# PowerSupply.net
KiCad netlist of a schematic drawn in Altium Designer
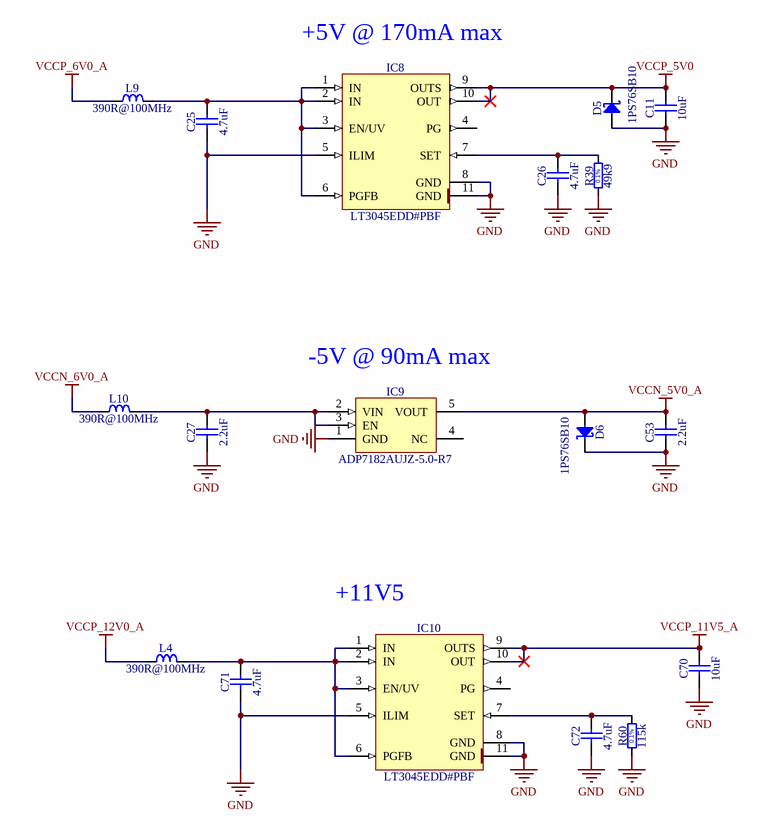
[diagram p0: PowerSupply.SchDoc]

(export (version "E")
  (design (tool "Eeschema 10.0.6"))
  (components
    (comp (ref "C11")
      (value "10uF")
      (footprint "CAPC1608X87N")
      (description "Non-polarised capacitor")
      (fields
        (field (name "PART NUMBER") "CC0603_10UF_6.3V_20%_X5R")
        (field (name "VOLTAGE") "6.3V")
        (field (name "AUTHOR") "CERN DEM JLC")
      )
      (libsource (lib "Capacitors") (part "Capacitor - non polarized"))
    )
    (comp (ref "C25")
      (value "4.7uF")
      (footprint "CAPC1709X95N")
      (description "Non-polarised capacitor")
      (fields
        (field (name "PART NUMBER") "CC0603_4.7UF_16V_10%_X5R")
        (field (name "VOLTAGE") "16V")
        (field (name "AUTHOR") "CERN DEM JLC")
      )
      (libsource (lib "Capacitors") (part "Capacitor - non polarized"))
    )
    (comp (ref "C26")
      (value "4.7uF")
      (footprint "CAPC1709X95N")
      (description "Non-polarised capacitor")
      (fields
        (field (name "PART NUMBER") "CC0603_4.7UF_16V_10%_X5R")
        (field (name "VOLTAGE") "16V")
        (field (name "AUTHOR") "CERN DEM JLC")
      )
      (libsource (lib "Capacitors") (part "Capacitor - non polarized"))
    )
    (comp (ref "C27")
      (value "2.2uF")
      (footprint "CAPC1608X90N")
      (description "Non-polarised capacitor")
      (fields
        (field (name "PART NUMBER") "CC0603_2.2UF_10V_20%_X7R")
        (field (name "VOLTAGE") "10V")
        (field (name "AUTHOR") "CERN DEM JLC")
      )
      (libsource (lib "Capacitors") (part "Capacitor - non polarized"))
    )
    (comp (ref "C53")
      (value "2.2uF")
      (footprint "CAPC1608X90N")
      (description "Non-polarised capacitor")
      (fields
        (field (name "PART NUMBER") "CC0603_2.2UF_10V_20%_X7R")
        (field (name "VOLTAGE") "10V")
        (field (name "AUTHOR") "CERN DEM JLC")
      )
      (libsource (lib "Capacitors") (part "Capacitor - non polarized"))
    )
    (comp (ref "C70")
      (value "10uF")
      (footprint "CAPC1608X87N")
      (description "Non-polarised capacitor")
      (fields
        (field (name "PART NUMBER") "CC0603_10UF_6.3V_20%_X5R")
        (field (name "VOLTAGE") "6.3V")
        (field (name "AUTHOR") "CERN DEM JLC")
      )
      (libsource (lib "Capacitors") (part "Capacitor - non polarized"))
    )
    (comp (ref "C71")
      (value "4.7uF")
      (footprint "CAPC1709X95N")
      (description "Non-polarised capacitor")
      (fields
        (field (name "PART NUMBER") "CC0603_4.7UF_16V_10%_X5R")
        (field (name "VOLTAGE") "16V")
        (field (name "AUTHOR") "CERN DEM JLC")
      )
      (libsource (lib "Capacitors") (part "Capacitor - non polarized"))
    )
    (comp (ref "C72")
      (value "4.7uF")
      (footprint "CAPC1709X95N")
      (description "Non-polarised capacitor")
      (fields
        (field (name "PART NUMBER") "CC0603_4.7UF_16V_10%_X5R")
        (field (name "VOLTAGE") "16V")
        (field (name "AUTHOR") "CERN DEM JLC")
      )
      (libsource (lib "Capacitors") (part "Capacitor - non polarized"))
    )
    (comp (ref "D5")
      (value "1PS76SB10")
      (footprint "SOD2512X110N")
      (description "Schottky Diode")
      (fields
        (field (name "VOLTAGE") "30V")
        (field (name "POWER") "200mA")
        (field (name "AUTHOR") "CERN DEM JLC")
      )
      (libsource (lib "ICs And Semiconductors") (part "Diode Schottky"))
    )
    (comp (ref "D6")
      (value "1PS76SB10")
      (footprint "SOD2512X110N")
      (description "Schottky Diode")
      (fields
        (field (name "VOLTAGE") "30V")
        (field (name "POWER") "200mA")
        (field (name "AUTHOR") "CERN DEM JLC")
      )
      (libsource (lib "ICs And Semiconductors") (part "Diode Schottky"))
    )
    (comp (ref "IC8")
      (value "LT3045EDD#PBF")
      (footprint "SON50P300X300X80-11N-R175X248")
      (description "20V, 500mA, Ultralow Noise, Ultrahigh PSRR Linear Regulator")
      (fields (field (name "MANUFACTURER") "LINEAR TECHNOLOGY") (field (name "AUTHOR") "CERN DEM JLC"))
      (libsource (lib "ICs And Semiconductors") (part "LT3045EDD"))
    )
    (comp (ref "IC9")
      (value "ADP7182AUJZ-5.0-R7")
      (footprint "SOT95P280X90-5N")
      (description "–5V, 200 mA, Low Noise, Linear Regulator")
      (fields (field (name "MANUFACTURER") "ANALOG DEVICES") (field (name "AUTHOR") "CERN DEM JLC"))
      (libsource (lib "ICs And Semiconductors") (part "ADP7182AUJZ-X.X-R7"))
    )
    (comp (ref "IC10")
      (value "LT3045EDD#PBF")
      (footprint "SON50P300X300X80-11N-R175X248")
      (description "20V, 500mA, Ultralow Noise, Ultrahigh PSRR Linear Regulator")
      (fields (field (name "MANUFACTURER") "LINEAR TECHNOLOGY") (field (name "AUTHOR") "CERN DEM JLC"))
      (libsource (lib "ICs And Semiconductors") (part "LT3045EDD"))
    )
    (comp (ref "L4")
      (value "390R@100MHz")
      (footprint "INDC1608X95N")
      (description "Inductor")
      (fields
        (field (name "PART NUMBER") "IND0603_TDK_MPZ1608R391A")
        (field (name "POWER") "1.2A")
        (field (name "AUTHOR") "CERN DEM JLC")
      )
      (libsource (lib "Inductors & Transformers") (part "Inductor"))
    )
    (comp (ref "L9")
      (value "390R@100MHz")
      (footprint "INDC1608X95N")
      (description "Inductor")
      (fields
        (field (name "PART NUMBER") "IND0603_TDK_MPZ1608R391A")
        (field (name "POWER") "1.2A")
        (field (name "AUTHOR") "CERN DEM JLC")
      )
      (libsource (lib "Inductors & Transformers") (part "Inductor"))
    )
    (comp (ref "L10")
      (value "390R@100MHz")
      (footprint "INDC1608X95N")
      (description "Inductor")
      (fields
        (field (name "PART NUMBER") "IND0603_TDK_MPZ1608R391A")
        (field (name "POWER") "1.2A")
        (field (name "AUTHOR") "CERN DEM JLC")
      )
      (libsource (lib "Inductors & Transformers") (part "Inductor"))
    )
    (comp (ref "R39")
      (value "49k9")
      (footprint "RESC1608X55N")
      (description "Resistor - 0.1%")
      (fields
        (field (name "PART NUMBER") "R0603_49K9_0.1%_0.063W_10PPM")
        (field (name "POWER") "0.063W")
        (field (name "AUTHOR") "CERN DEM JLC")
      )
      (libsource (lib "Resistors") (part "Resistor - 0.1%"))
    )
    (comp (ref "R60")
      (value "115k")
      (footprint "RESC1608X55N")
      (description "Resistor - 0.1%")
      (fields
        (field (name "PART NUMBER") "R0603_115K_0.1%_0.063W_10PPM")
        (field (name "POWER") "0.063W")
        (field (name "AUTHOR") "CERN DEM JLC")
      )
      (libsource (lib "Resistors") (part "Resistor - 0.1%"))
    )
  )
  (nets
    (net (code "1") (name "GND") (class "Default")
      (node (ref "C11") (pin "1") (pinfunction "1_1") (pintype "passive"))
      (node (ref "C25") (pin "1") (pinfunction "1_1") (pintype "passive"))
      (node (ref "C26") (pin "1") (pinfunction "1_1") (pintype "passive"))
      (node (ref "C27") (pin "1") (pinfunction "1_1") (pintype "passive"))
      (node (ref "C53") (pin "1") (pinfunction "1_1") (pintype "passive"))
      (node (ref "C70") (pin "1") (pinfunction "1_1") (pintype "passive"))
      (node (ref "C71") (pin "1") (pinfunction "1_1") (pintype "passive"))
      (node (ref "C72") (pin "1") (pinfunction "1_1") (pintype "passive"))
      (node (ref "D5") (pin "2") (pinfunction "A_2") (pintype "passive"))
      (node (ref "D6") (pin "1") (pinfunction "C_1") (pintype "passive"))
      (node (ref "IC10") (pin "11") (pinfunction "GND_11") (pintype "power_in"))
      (node (ref "IC10") (pin "5") (pinfunction "ILIM_5") (pintype "input"))
      (node (ref "IC10") (pin "8") (pinfunction "GND_8") (pintype "power_in"))
      (node (ref "IC8") (pin "11") (pinfunction "GND_11") (pintype "power_in"))
      (node (ref "IC8") (pin "5") (pinfunction "ILIM_5") (pintype "input"))
      (node (ref "IC8") (pin "8") (pinfunction "GND_8") (pintype "power_in"))
      (node (ref "IC9") (pin "1") (pinfunction "GND_1") (pintype "power_in"))
      (node (ref "R39") (pin "1") (pinfunction "1_1") (pintype "passive"))
      (node (ref "R60") (pin "1") (pinfunction "1_1") (pintype "passive"))
    )
    (net (code "2") (name "Net-(IC8-EN{slash}UV)") (class "Default")
      (node (ref "C25") (pin "2") (pinfunction "2_2") (pintype "passive"))
      (node (ref "IC8") (pin "1") (pinfunction "IN_1") (pintype "input"))
      (node (ref "IC8") (pin "2") (pinfunction "IN_2") (pintype "input"))
      (node (ref "IC8") (pin "3") (pinfunction "EN/UV_3") (pintype "input"))
      (node (ref "IC8") (pin "6") (pinfunction "PGFB_6") (pintype "input"))
      (node (ref "L9") (pin "2") (pinfunction "2_2") (pintype "passive"))
    )
    (net (code "3") (name "Net-(IC8-SET)") (class "Default")
      (node (ref "C26") (pin "2") (pinfunction "2_2") (pintype "passive"))
      (node (ref "IC8") (pin "7") (pinfunction "SET_7") (pintype "input"))
      (node (ref "R39") (pin "2") (pinfunction "2_2") (pintype "passive"))
    )
    (net (code "4") (name "Net-(IC9-EN)") (class "Default")
      (node (ref "C27") (pin "2") (pinfunction "2_2") (pintype "passive"))
      (node (ref "IC9") (pin "2") (pinfunction "VIN_2") (pintype "input"))
      (node (ref "IC9") (pin "3") (pinfunction "EN_3") (pintype "input"))
      (node (ref "L10") (pin "2") (pinfunction "2_2") (pintype "passive"))
    )
    (net (code "5") (name "Net-(IC10-EN{slash}UV)") (class "Default")
      (node (ref "C71") (pin "2") (pinfunction "2_2") (pintype "passive"))
      (node (ref "IC10") (pin "1") (pinfunction "IN_1") (pintype "input"))
      (node (ref "IC10") (pin "2") (pinfunction "IN_2") (pintype "input"))
      (node (ref "IC10") (pin "3") (pinfunction "EN/UV_3") (pintype "input"))
      (node (ref "IC10") (pin "6") (pinfunction "PGFB_6") (pintype "input"))
      (node (ref "L4") (pin "2") (pinfunction "2_2") (pintype "passive"))
    )
    (net (code "6") (name "Net-(IC10-SET)") (class "Default")
      (node (ref "C72") (pin "2") (pinfunction "2_2") (pintype "passive"))
      (node (ref "IC10") (pin "7") (pinfunction "SET_7") (pintype "input"))
      (node (ref "R60") (pin "2") (pinfunction "2_2") (pintype "passive"))
    )
    (net (code "7") (name "VCCN_5V0_A") (class "Default")
      (node (ref "C53") (pin "2") (pinfunction "2_2") (pintype "passive"))
      (node (ref "D6") (pin "2") (pinfunction "A_2") (pintype "passive"))
      (node (ref "IC9") (pin "5") (pinfunction "VOUT_5") (pintype "power_in"))
    )
    (net (code "8") (name "VCCN_6V0_A") (class "Default")
      (node (ref "L10") (pin "1") (pinfunction "1_1") (pintype "passive"))
    )
    (net (code "9") (name "VCCP_5V0") (class "Default")
      (node (ref "C11") (pin "2") (pinfunction "2_2") (pintype "passive"))
      (node (ref "D5") (pin "1") (pinfunction "C_1") (pintype "passive"))
      (node (ref "IC8") (pin "10") (pinfunction "OUT_10") (pintype "output"))
      (node (ref "IC8") (pin "9") (pinfunction "OUTS_9") (pintype "output"))
    )
    (net (code "10") (name "VCCP_6V0_A") (class "Default")
      (node (ref "L9") (pin "1") (pinfunction "1_1") (pintype "passive"))
    )
    (net (code "11") (name "VCCP_11V5_A") (class "Default")
      (node (ref "C70") (pin "2") (pinfunction "2_2") (pintype "passive"))
      (node (ref "IC10") (pin "10") (pinfunction "OUT_10") (pintype "output"))
      (node (ref "IC10") (pin "9") (pinfunction "OUTS_9") (pintype "output"))
    )
    (net (code "12") (name "VCCP_12V0_A") (class "Default")
      (node (ref "L4") (pin "1") (pinfunction "1_1") (pintype "passive"))
    )
    (net (code "13") (name "unconnected-(IC8-PG-Pad4)") (class "Default")
      (node (ref "IC8") (pin "4") (pinfunction "PG_4") (pintype "output"))
    )
    (net (code "14") (name "unconnected-(IC9-NC-Pad4)") (class "Default")
      (node (ref "IC9") (pin "4") (pinfunction "NC_4") (pintype "passive"))
    )
    (net (code "15") (name "unconnected-(IC10-PG-Pad4)") (class "Default")
      (node (ref "IC10") (pin "4") (pinfunction "PG_4") (pintype "output"))
    )
  )
)
